# RGBParkLight.net
KiCad netlist of a schematic drawn in Altium Designer
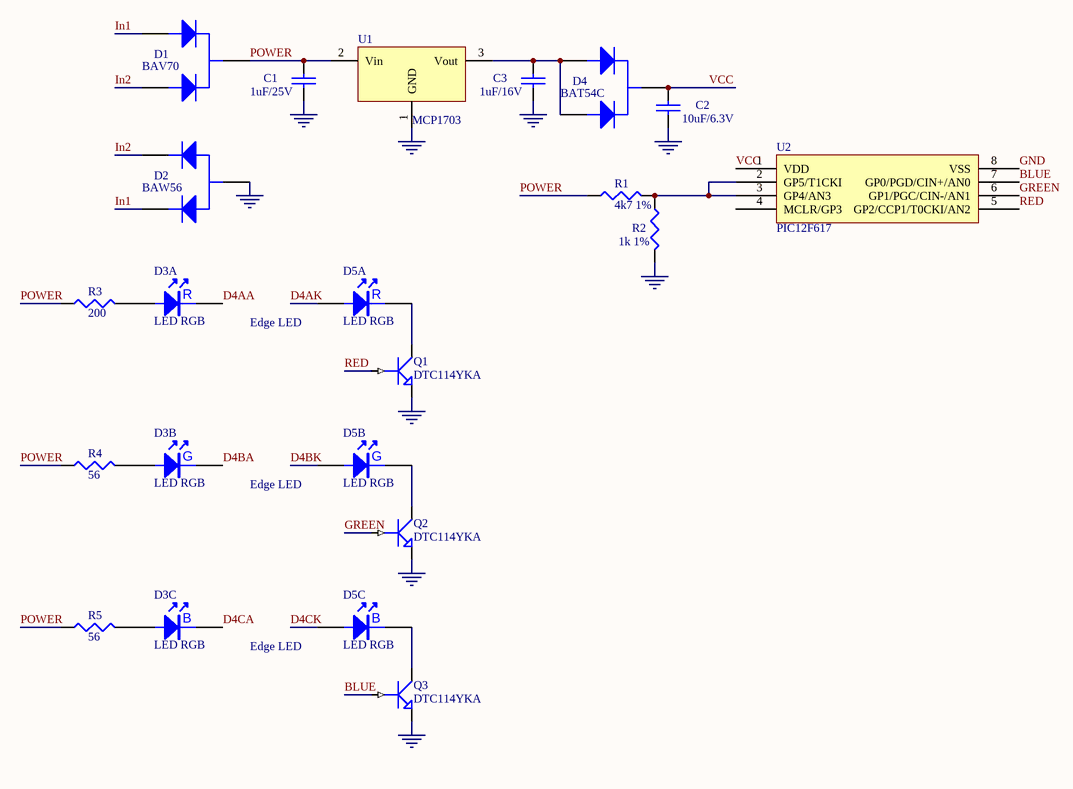
[diagram p0: RGBParkLight.SCHDOC]

(export (version "E")
  (design (tool "Eeschema 10.0.6"))
  (components
    (comp (ref "C1")
      (value "1uF/25V")
      (footprint "0805")
      (description "Capacitor")
      (libsource (lib "Miscellaneous Devices") (part "CAP"))
    )
    (comp (ref "C2")
      (value "10uF/6.3V")
      (footprint "0805")
      (description "Capacitor")
      (libsource (lib "Miscellaneous Devices") (part "CAP"))
    )
    (comp (ref "C3")
      (value "1uF/16V")
      (footprint "0603")
      (description "Capacitor")
      (libsource (lib "Miscellaneous Devices") (part "CAP"))
    )
    (comp (ref "D1")
      (value "BAV70")
      (footprint "SOT-23")
      (libsource (lib "Devices") (part "DUAL DIODE BAV70"))
    )
    (comp (ref "D2")
      (value "BAW56")
      (footprint "SOT-23")
      (libsource (lib "Devices") (part "DUAL DIODE BAW56"))
    )
    (comp (ref "D3") (value "~") (footprint "AF-5060") (libsource (lib "Devices") (part "LED RGB")))
    (comp (ref "D4")
      (value "BAT54C")
      (footprint "SOT-23")
      (libsource (lib "Devices") (part "DUAL DIODE BAV70"))
    )
    (comp (ref "D5") (value "~") (footprint "AF-5060") (libsource (lib "Devices") (part "LED RGB")))
    (comp (ref "Q1")
      (value "DTC114YKA")
      (footprint "SOT-23")
      (description "NPN Transistor")
      (libsource (lib "Miscellaneous Devices") (part "NPN1"))
    )
    (comp (ref "Q2")
      (value "DTC114YKA")
      (footprint "SOT-23")
      (description "NPN Transistor")
      (libsource (lib "Miscellaneous Devices") (part "NPN1"))
    )
    (comp (ref "Q3")
      (value "DTC114YKA")
      (footprint "SOT-23")
      (description "NPN Transistor")
      (libsource (lib "Miscellaneous Devices") (part "NPN1"))
    )
    (comp (ref "R1")
      (value "4k7 1%")
      (footprint "0603")
      (libsource (lib "Miscellaneous Devices") (part "RES1"))
    )
    (comp (ref "R2")
      (value "1k 1%")
      (footprint "0603")
      (libsource (lib "Miscellaneous Devices") (part "RES1"))
    )
    (comp (ref "R3") (value "200") (footprint "0805") (libsource (lib "Miscellaneous Devices") (part "RES1")))
    (comp (ref "R4") (value "56") (footprint "0805") (libsource (lib "Miscellaneous Devices") (part "RES1")))
    (comp (ref "R5") (value "56") (footprint "0805") (libsource (lib "Miscellaneous Devices") (part "RES1")))
    (comp (ref "U1")
      (value "MCP1703")
      (footprint "SOT-23")
      (libsource (lib "Miscellaneous Devices") (part "VOLTREG"))
    )
    (comp (ref "U2") (value "PIC12F617") (footprint "SO-8") (libsource (lib "MCU") (part "PIC12F683")))
  )
  (nets
    (net (code "1") (name "/BLUE") (class "Default")
      (node (ref "Q3") (pin "1") (pinfunction "B_1") (pintype "input"))
      (node (ref "U2") (pin "7") (pinfunction "GP0/PGD/CIN+/AN0_7") (pintype "passive"))
    )
    (net (code "2") (name "/D4AA") (class "Default")
      (node (ref "D3") (pin "4") (pinfunction "K_4") (pintype "passive"))
    )
    (net (code "3") (name "/D4AK") (class "Default")
      (node (ref "D5") (pin "3") (pinfunction "A_3") (pintype "passive"))
    )
    (net (code "4") (name "/D4BA") (class "Default")
      (node (ref "D3") (pin "5") (pinfunction "K_5") (pintype "passive"))
    )
    (net (code "5") (name "/D4BK") (class "Default")
      (node (ref "D5") (pin "2") (pinfunction "A_2") (pintype "passive"))
    )
    (net (code "6") (name "/D4CA") (class "Default")
      (node (ref "D3") (pin "6") (pinfunction "K_6") (pintype "passive"))
    )
    (net (code "7") (name "/D4CK") (class "Default")
      (node (ref "D5") (pin "1") (pinfunction "A_1") (pintype "passive"))
    )
    (net (code "8") (name "/GREEN") (class "Default")
      (node (ref "Q2") (pin "1") (pinfunction "B_1") (pintype "input"))
      (node (ref "U2") (pin "6") (pinfunction "GP1/PGC/CIN-/AN1_6") (pintype "passive"))
    )
    (net (code "9") (name "/In1") (class "Default")
      (node (ref "D1") (pin "1") (pinfunction "A1_1") (pintype "passive"))
      (node (ref "D2") (pin "3") (pinfunction "K2_3") (pintype "passive"))
    )
    (net (code "10") (name "/In2") (class "Default")
      (node (ref "D1") (pin "3") (pinfunction "A2_3") (pintype "passive"))
      (node (ref "D2") (pin "1") (pinfunction "K1_1") (pintype "passive"))
    )
    (net (code "11") (name "/POWER") (class "Default")
      (node (ref "C1") (pin "1") (pinfunction "1_1") (pintype "passive"))
      (node (ref "D1") (pin "2") (pinfunction "K_2") (pintype "passive"))
      (node (ref "R1") (pin "1") (pinfunction "1_1") (pintype "passive"))
      (node (ref "R3") (pin "1") (pinfunction "1_1") (pintype "passive"))
      (node (ref "R4") (pin "1") (pinfunction "1_1") (pintype "passive"))
      (node (ref "R5") (pin "1") (pinfunction "1_1") (pintype "passive"))
      (node (ref "U1") (pin "2") (pinfunction "Vin_2") (pintype "passive"))
    )
    (net (code "12") (name "/RED") (class "Default")
      (node (ref "Q1") (pin "1") (pinfunction "B_1") (pintype "input"))
      (node (ref "U2") (pin "5") (pinfunction "GP2/CCP1/T0CKI/AN2_5") (pintype "passive"))
    )
    (net (code "13") (name "/VCC") (class "Default")
      (node (ref "C2") (pin "1") (pinfunction "1_1") (pintype "passive"))
      (node (ref "D4") (pin "2") (pinfunction "K_2") (pintype "passive"))
      (node (ref "U2") (pin "1") (pinfunction "VDD_1") (pintype "passive"))
    )
    (net (code "14") (name "GND") (class "Default")
      (node (ref "C1") (pin "2") (pinfunction "2_2") (pintype "passive"))
      (node (ref "C2") (pin "2") (pinfunction "2_2") (pintype "passive"))
      (node (ref "C3") (pin "2") (pinfunction "2_2") (pintype "passive"))
      (node (ref "D2") (pin "2") (pinfunction "A_2") (pintype "passive"))
      (node (ref "Q1") (pin "3") (pinfunction "E_3") (pintype "passive"))
      (node (ref "Q2") (pin "3") (pinfunction "E_3") (pintype "passive"))
      (node (ref "Q3") (pin "3") (pinfunction "E_3") (pintype "passive"))
      (node (ref "R2") (pin "2") (pinfunction "2_2") (pintype "passive"))
      (node (ref "U1") (pin "1") (pinfunction "GND_1") (pintype "passive"))
      (node (ref "U2") (pin "8") (pinfunction "VSS_8") (pintype "passive"))
    )
    (net (code "15") (name "Net-(D3A-A)") (class "Default")
      (node (ref "D3") (pin "3") (pinfunction "A_3") (pintype "passive"))
      (node (ref "R3") (pin "2") (pinfunction "2_2") (pintype "passive"))
    )
    (net (code "16") (name "Net-(D3B-A)") (class "Default")
      (node (ref "D3") (pin "2") (pinfunction "A_2") (pintype "passive"))
      (node (ref "R4") (pin "2") (pinfunction "2_2") (pintype "passive"))
    )
    (net (code "17") (name "Net-(D3C-A)") (class "Default")
      (node (ref "D3") (pin "1") (pinfunction "A_1") (pintype "passive"))
      (node (ref "R5") (pin "2") (pinfunction "2_2") (pintype "passive"))
    )
    (net (code "18") (name "Net-(D4-A1)") (class "Default")
      (node (ref "C3") (pin "1") (pinfunction "1_1") (pintype "passive"))
      (node (ref "D4") (pin "1") (pinfunction "A1_1") (pintype "passive"))
      (node (ref "D4") (pin "3") (pinfunction "A2_3") (pintype "passive"))
      (node (ref "U1") (pin "3") (pinfunction "Vout_3") (pintype "passive"))
    )
    (net (code "19") (name "Net-(D5A-K)") (class "Default")
      (node (ref "D5") (pin "4") (pinfunction "K_4") (pintype "passive"))
      (node (ref "Q1") (pin "2") (pinfunction "C_2") (pintype "passive"))
    )
    (net (code "20") (name "Net-(D5B-K)") (class "Default")
      (node (ref "D5") (pin "5") (pinfunction "K_5") (pintype "passive"))
      (node (ref "Q2") (pin "2") (pinfunction "C_2") (pintype "passive"))
    )
    (net (code "21") (name "Net-(D5C-K)") (class "Default")
      (node (ref "D5") (pin "6") (pinfunction "K_6") (pintype "passive"))
      (node (ref "Q3") (pin "2") (pinfunction "C_2") (pintype "passive"))
    )
    (net (code "22") (name "Net-(U2-GP4{slash}AN3)") (class "Default")
      (node (ref "R1") (pin "2") (pinfunction "2_2") (pintype "passive"))
      (node (ref "R2") (pin "1") (pinfunction "1_1") (pintype "passive"))
      (node (ref "U2") (pin "2") (pinfunction "GP5/T1CKI_2") (pintype "passive"))
      (node (ref "U2") (pin "3") (pinfunction "GP4/AN3_3") (pintype "passive"))
    )
    (net (code "23") (name "unconnected-(U2-MCLR{slash}GP3-Pad4)") (class "Default")
      (node (ref "U2") (pin "4") (pinfunction "MCLR/GP3_4") (pintype "passive"))
    )
  )
)
